# LcsNodes-Main-Controller-Board-B_02_01.net
KiCad netlist of a schematic drawn in EasyEDA
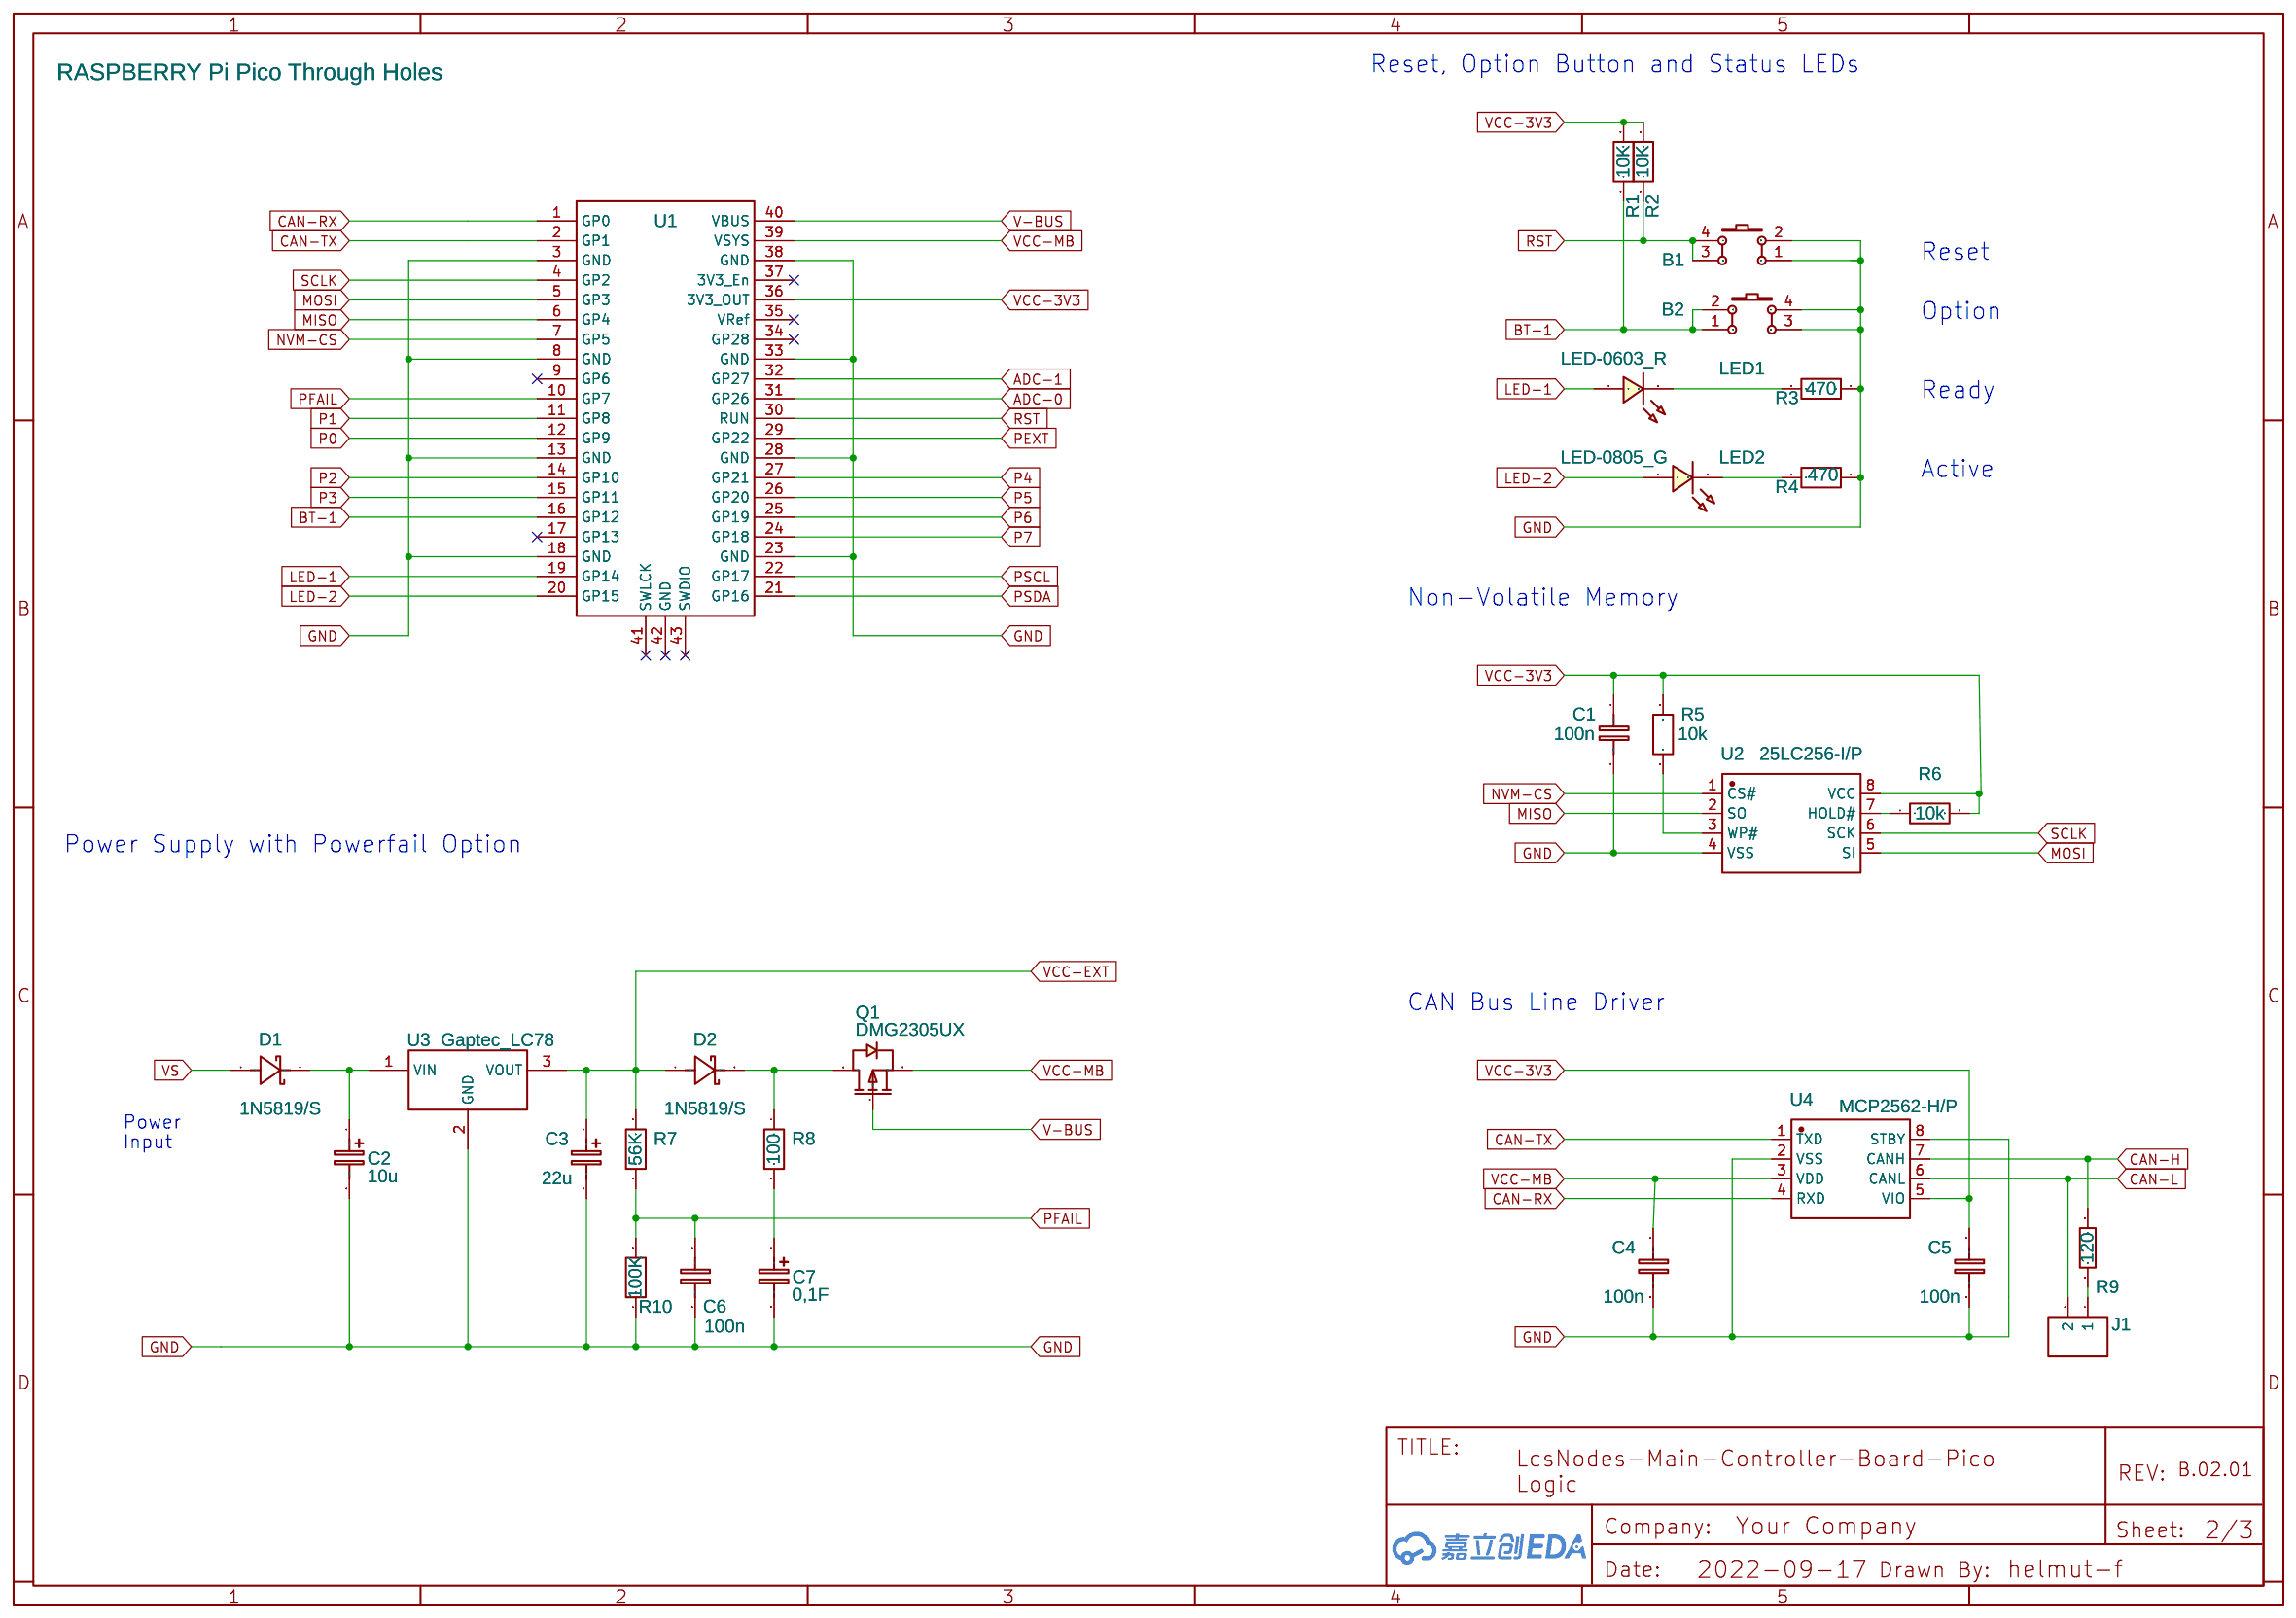
[diagram p0: Controller]
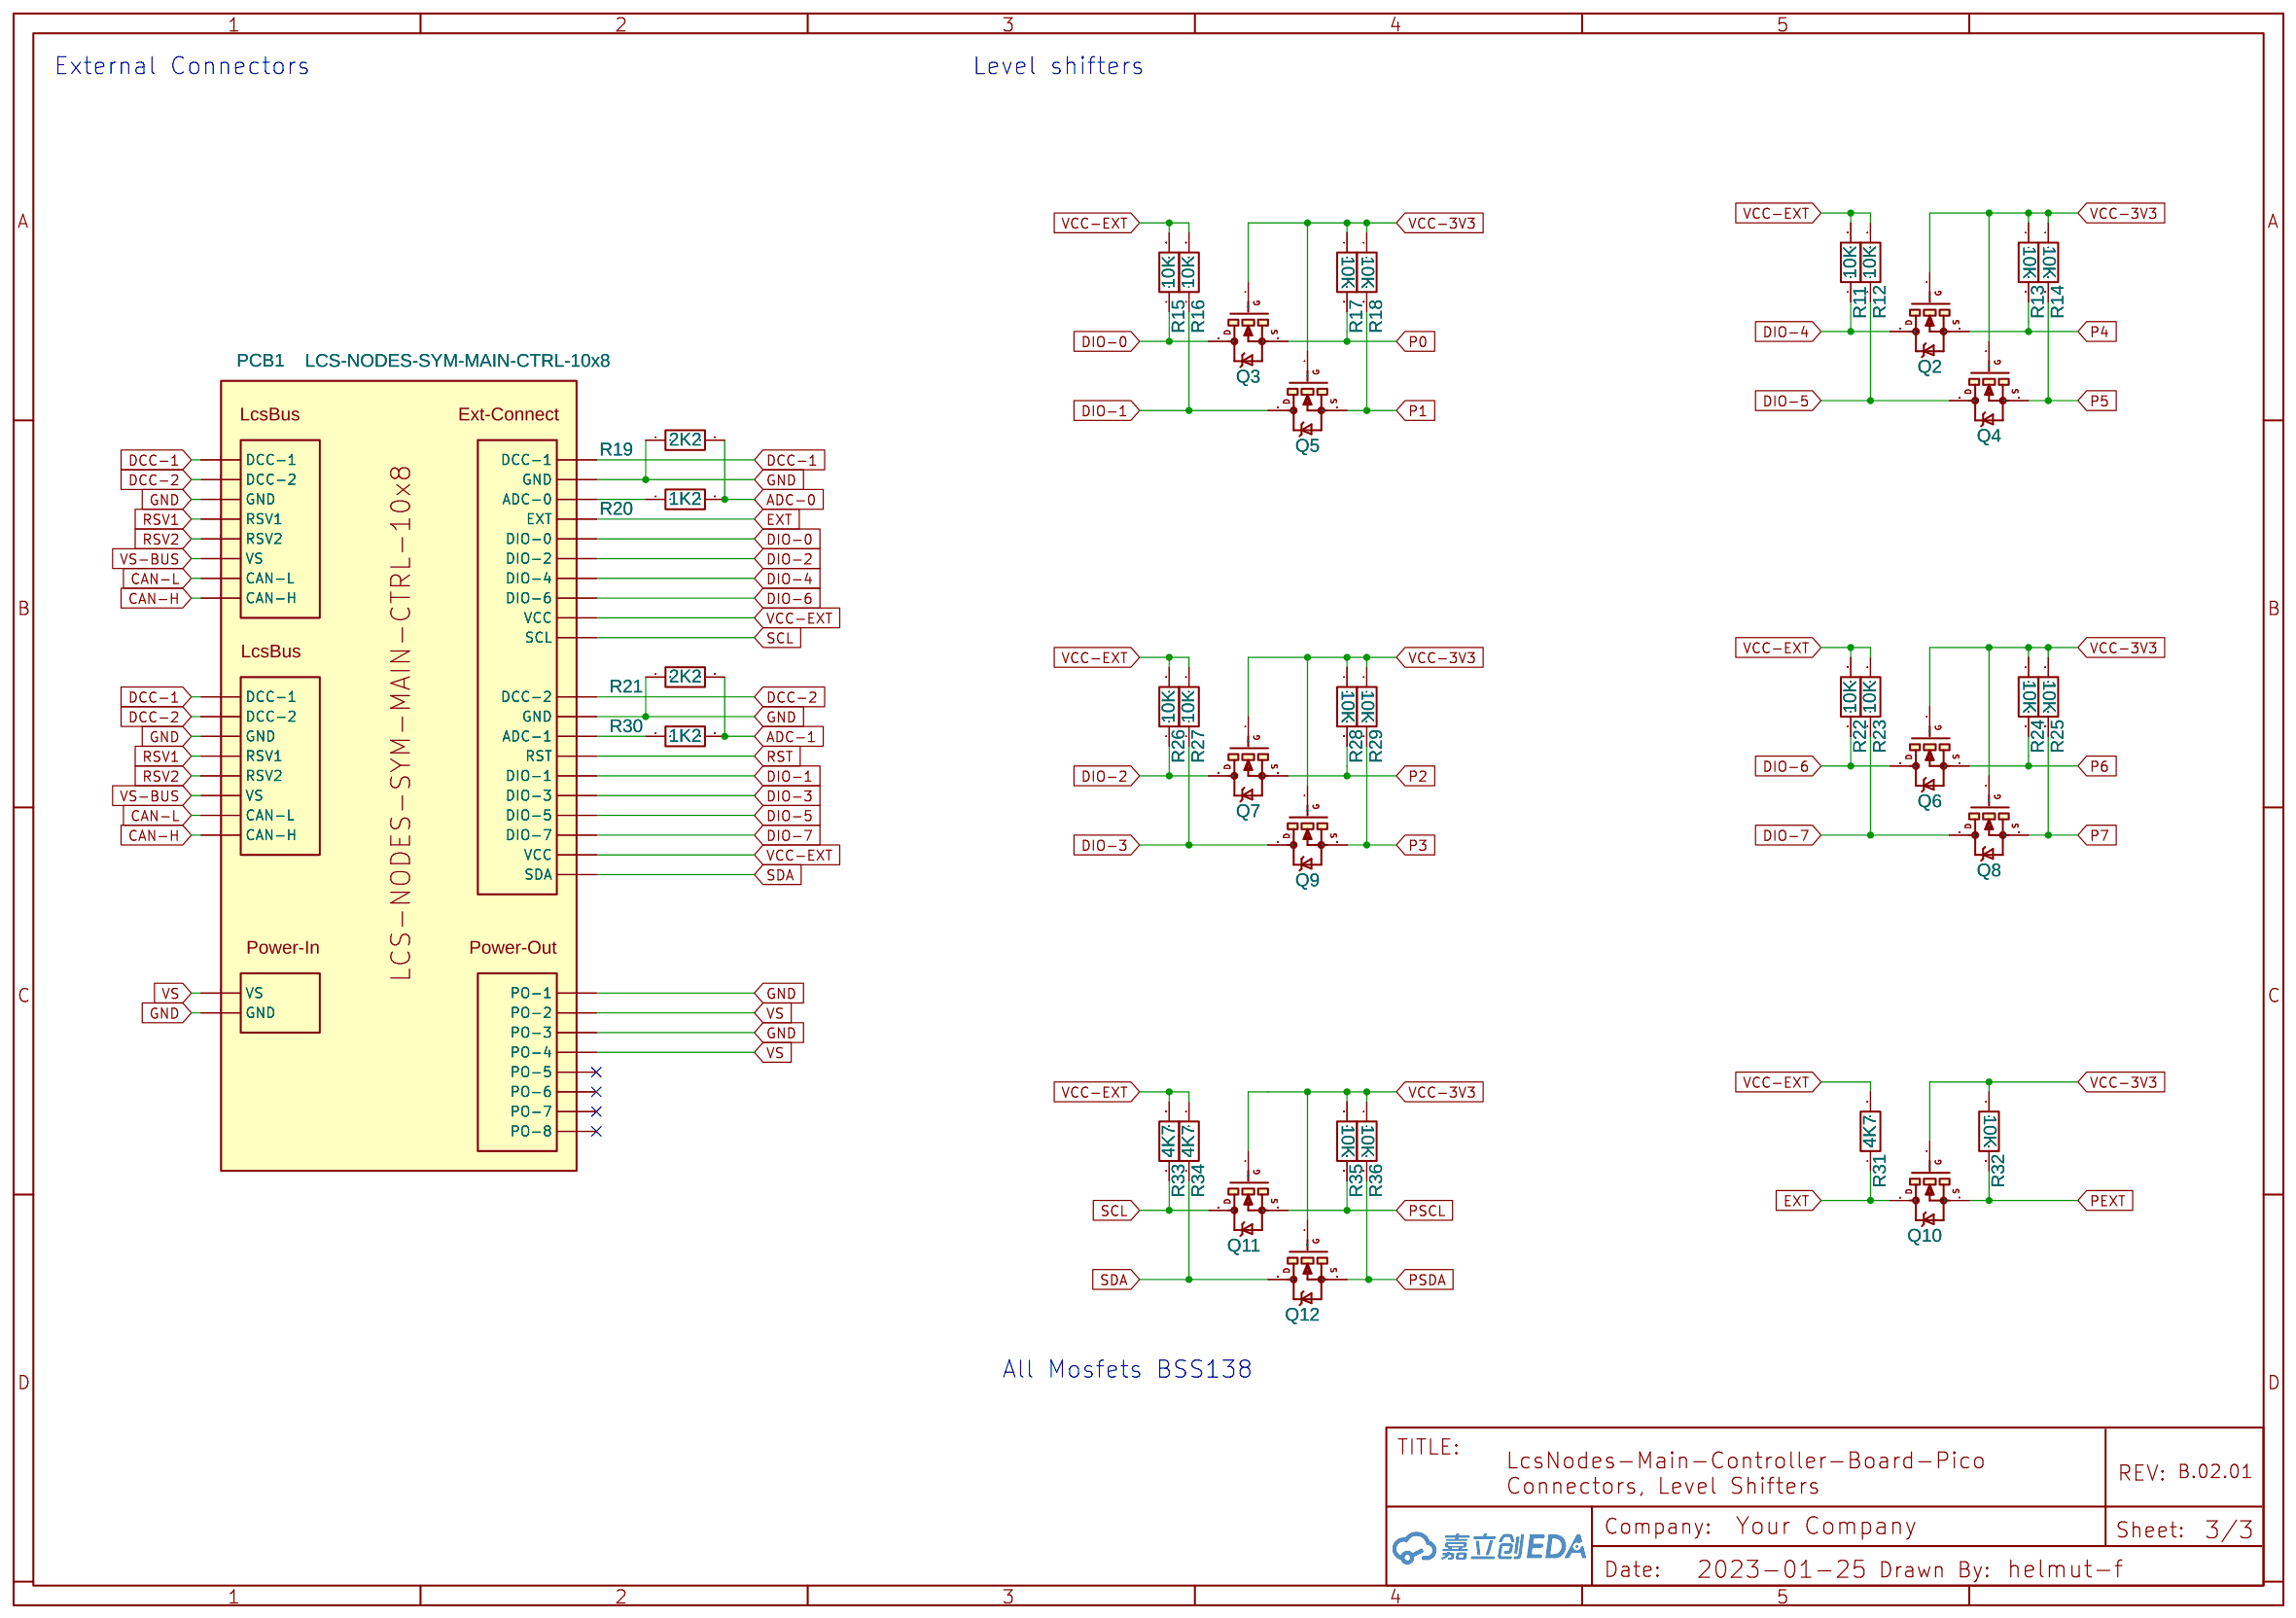
[diagram p1: Connector]
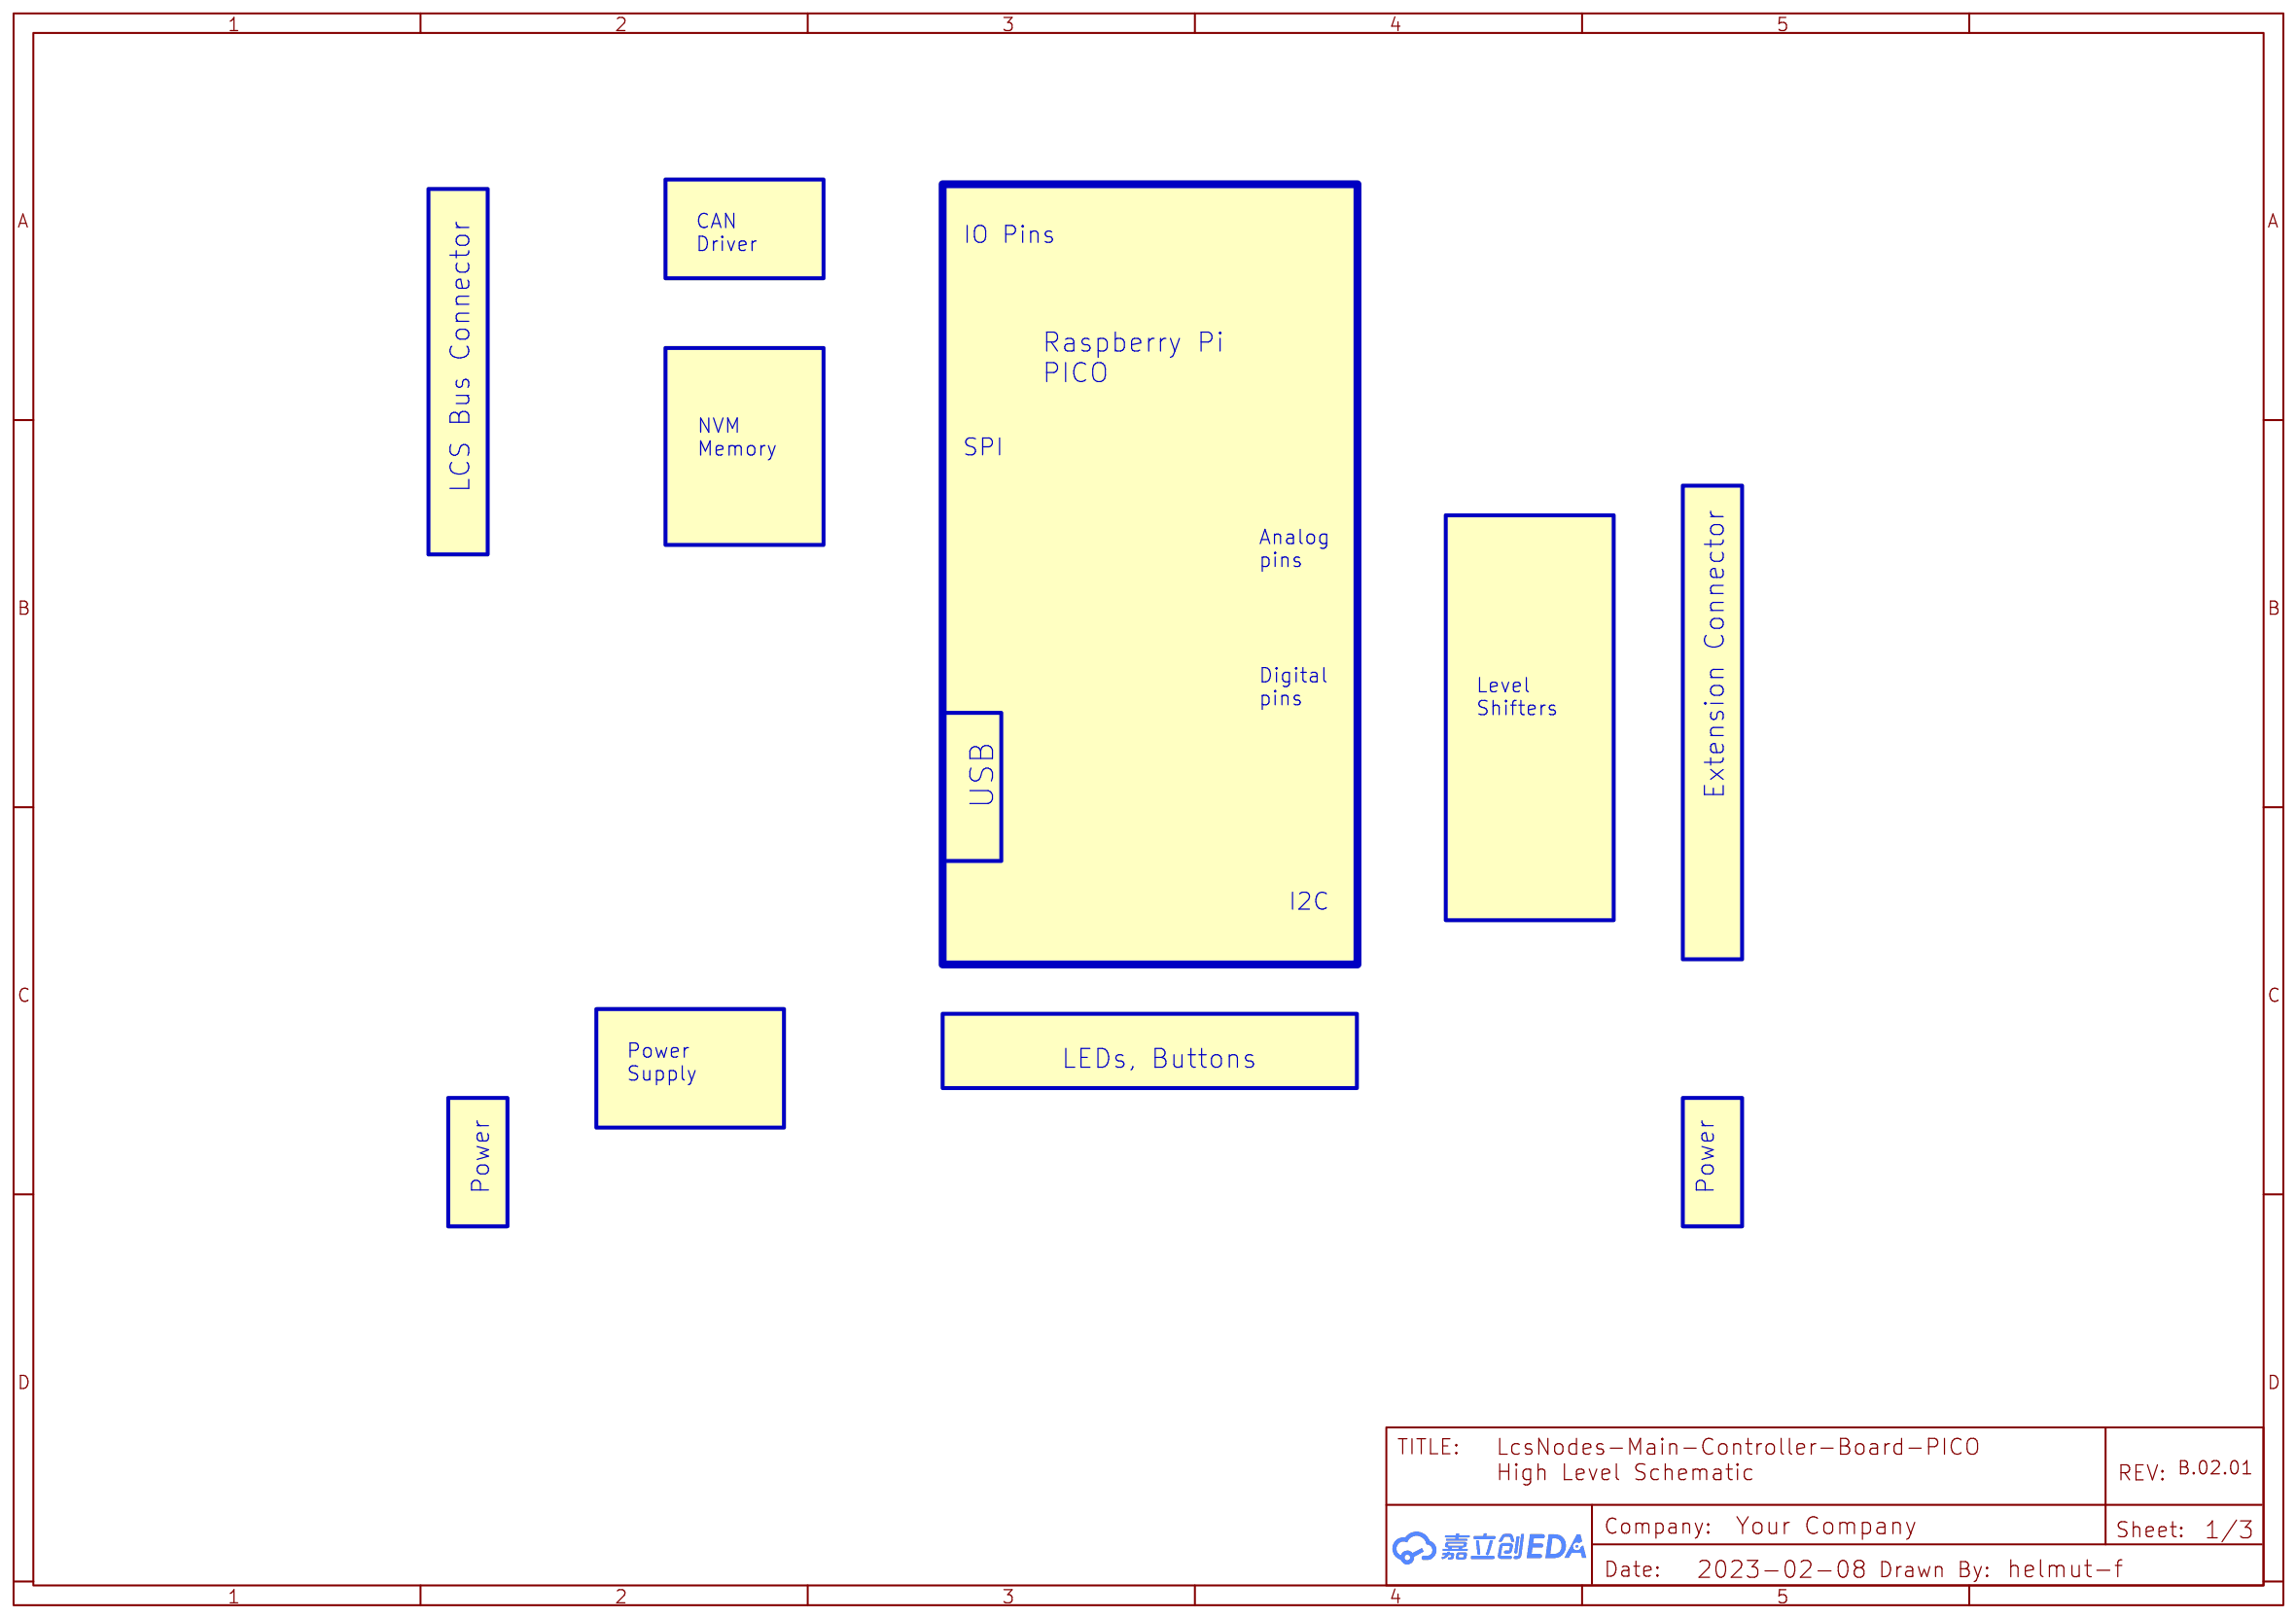
[diagram p2: Block Diagram]

(export (version "E")
  (design (tool "Eeschema 10.0.6"))
  (components
    (comp (ref "B1")
      (value "Reset")
      (fields (field (name "Manufacturer Part") "K2-1102DP-E4SW-04") (field (name "Manufacturer") "韩国韩荣"))
      (libsource (lib "") (part "K4-6×6_TH_1"))
    )
    (comp (ref "B2")
      (value "Opt")
      (fields (field (name "Manufacturer Part") "K2-1102DP-E4SW-04") (field (name "Manufacturer") "韩国韩荣"))
      (libsource (lib "") (part "K4-6×6_TH"))
    )
    (comp (ref "C1") (value "100n") (libsource (lib "") (part "C_0603_EU_1")))
    (comp (ref "C2") (value "10u") (libsource (lib "") (part "CE_SMD_D5.0×H5.5_EU_1")))
    (comp (ref "C3") (value "22u") (libsource (lib "") (part "CE_SMD_D5.0×H5.5_EU")))
    (comp (ref "C4") (value "100n") (libsource (lib "") (part "C_0603_EU")))
    (comp (ref "C5") (value "100n") (libsource (lib "") (part "C_0603_EU")))
    (comp (ref "C6") (value "100n") (libsource (lib "") (part "C_RAD-0.2_EU")))
    (comp (ref "C7") (value "0,1F") (libsource (lib "") (part "C_Tan_SMD_A_EU")))
    (comp (ref "D1") (value "1N5819/S") (libsource (lib "") (part "1N5819/S")))
    (comp (ref "D2") (value "1N5819/S") (libsource (lib "") (part "1N5819/S")))
    (comp (ref "J1") (value "HDR-M-2.54_1x2") (libsource (lib "") (part "HDR-M-2.54_1x2")))
    (comp (ref "LED1")
      (value "LED-0603_R")
      (fields
        (field (name "Manufacturer Part") "19-217/R6C-AL1M2VY/3T")
        (field (name "Manufacturer") "EVERLIGHT(台湾亿光)")
      )
      (libsource (lib "") (part "LED-0603_R"))
    )
    (comp (ref "LED2")
      (value "LED-0805_G")
      (fields (field (name "Manufacturer Part") "NCD0805G1") (field (name "Manufacturer") "国星光电"))
      (libsource (lib "") (part "LED-0805_G"))
    )
    (comp (ref "Q1")
      (value "DMG2305UX")
      (fields (field (name "Manufacturer") "TECH PUBLIC(台舟)"))
      (libsource (lib "") (part "DMG2305UX"))
    )
    (comp (ref "R1") (value "10K") (libsource (lib "") (part "R_0805_EU")))
    (comp (ref "R2") (value "10K") (libsource (lib "") (part "R_0805_EU")))
    (comp (ref "R3") (value "470") (libsource (lib "") (part "R_0805_EU_1")))
    (comp (ref "R4") (value "470") (libsource (lib "") (part "R_0805_EU_1")))
    (comp (ref "R5") (value "10k") (libsource (lib "") (part "R_AXIAL-0.3_EU_2")))
    (comp (ref "R6") (value "10k") (libsource (lib "") (part "R_AXIAL-0.3_EU")))
    (comp (ref "R7") (value "56K") (libsource (lib "") (part "R_AXIAL-0.3_EU_1")))
    (comp (ref "R8") (value "100") (libsource (lib "") (part "R_AXIAL-0.3_EU_2")))
    (comp (ref "R9") (value "120") (libsource (lib "") (part "RESISTOR-AXIAL-0.1")))
    (comp (ref "R10") (value "100K") (libsource (lib "") (part "R_AXIAL-0.3_EU_1")))
    (comp (ref "U1")
      (value "RASPBERRY Pi Pico Through Holes")
      (libsource (lib "") (part "RASPBERRY Pi Pico Through Holes"))
    )
    (comp (ref "U2")
      (value "25LC256-I/P")
      (fields (field (name "Manufacturer") "Microchip Tech"))
      (libsource (lib "") (part "25LC256-I/P"))
    )
    (comp (ref "U3") (value "Gaptec_LC78") (libsource (lib "") (part "Gaptec_LC78")))
    (comp (ref "U4")
      (value "MCP2562-H/P")
      (fields (field (name "Manufacturer") "MICROCHIP(美国微芯)"))
      (libsource (lib "") (part "MCP2562-H/P"))
    )
    (comp (ref "PCB1")
      (value "LCS-NODES-SYM-MAIN-CTRL-10x8")
      (libsource (lib "") (part "LCS-NODES-SYM-MAIN-CTRL-10x8"))
    )
    (comp (ref "Q2") (value "MOSFET-NCHANNELBSS138") (libsource (lib "") (part "MOSFET-NCHANNELBSS138")))
    (comp (ref "Q3") (value "MOSFET-NCHANNELBSS138") (libsource (lib "") (part "MOSFET-NCHANNELBSS138")))
    (comp (ref "Q4") (value "MOSFET-NCHANNELBSS138") (libsource (lib "") (part "MOSFET-NCHANNELBSS138")))
    (comp (ref "Q5") (value "MOSFET-NCHANNELBSS138") (libsource (lib "") (part "MOSFET-NCHANNELBSS138")))
    (comp (ref "Q6") (value "MOSFET-NCHANNELBSS138") (libsource (lib "") (part "MOSFET-NCHANNELBSS138")))
    (comp (ref "Q7") (value "MOSFET-NCHANNELBSS138") (libsource (lib "") (part "MOSFET-NCHANNELBSS138")))
    (comp (ref "Q8") (value "MOSFET-NCHANNELBSS138") (libsource (lib "") (part "MOSFET-NCHANNELBSS138")))
    (comp (ref "Q9") (value "MOSFET-NCHANNELBSS138") (libsource (lib "") (part "MOSFET-NCHANNELBSS138")))
    (comp (ref "Q10") (value "MOSFET-NCHANNELBSS138") (libsource (lib "") (part "MOSFET-NCHANNELBSS138")))
    (comp (ref "Q11") (value "MOSFET-NCHANNELBSS138") (libsource (lib "") (part "MOSFET-NCHANNELBSS138")))
    (comp (ref "Q12") (value "MOSFET-NCHANNELBSS138") (libsource (lib "") (part "MOSFET-NCHANNELBSS138")))
    (comp (ref "R11") (value "10K") (libsource (lib "") (part "R_0805_EU")))
    (comp (ref "R12") (value "10K") (libsource (lib "") (part "R_0805_EU")))
    (comp (ref "R13") (value "10K") (libsource (lib "") (part "R_0805_EU_1")))
    (comp (ref "R14") (value "10K") (libsource (lib "") (part "R_0805_EU_1")))
    (comp (ref "R15") (value "10K") (libsource (lib "") (part "R_0805_EU")))
    (comp (ref "R16") (value "10K") (libsource (lib "") (part "R_0805_EU")))
    (comp (ref "R17") (value "10K") (libsource (lib "") (part "R_0805_EU_1")))
    (comp (ref "R18") (value "10K") (libsource (lib "") (part "R_0805_EU_1")))
    (comp (ref "R19") (value "2K2") (libsource (lib "") (part "R_AXIAL-0.3_EU")))
    (comp (ref "R20") (value "1K2") (libsource (lib "") (part "R_AXIAL-0.3_EU")))
    (comp (ref "R21") (value "2K2") (libsource (lib "") (part "R_AXIAL-0.3_EU")))
    (comp (ref "R22") (value "10K") (libsource (lib "") (part "R_0805_EU")))
    (comp (ref "R23") (value "10K") (libsource (lib "") (part "R_0805_EU")))
    (comp (ref "R24") (value "10K") (libsource (lib "") (part "R_0805_EU_1")))
    (comp (ref "R25") (value "10K") (libsource (lib "") (part "R_0805_EU_1")))
    (comp (ref "R26") (value "10K") (libsource (lib "") (part "R_0805_EU")))
    (comp (ref "R27") (value "10K") (libsource (lib "") (part "R_0805_EU")))
    (comp (ref "R28") (value "10K") (libsource (lib "") (part "R_0805_EU_1")))
    (comp (ref "R29") (value "10K") (libsource (lib "") (part "R_0805_EU_1")))
    (comp (ref "R30") (value "1K2") (libsource (lib "") (part "R_AXIAL-0.3_EU")))
    (comp (ref "R31") (value "4K7") (libsource (lib "") (part "R_0805_EU")))
    (comp (ref "R32") (value "10K") (libsource (lib "") (part "R_0805_EU_1")))
    (comp (ref "R33") (value "4K7") (libsource (lib "") (part "R_0805_EU")))
    (comp (ref "R34") (value "4K7") (libsource (lib "") (part "R_0805_EU")))
    (comp (ref "R35") (value "10K") (libsource (lib "") (part "R_0805_EU_1")))
    (comp (ref "R36") (value "10K") (libsource (lib "") (part "R_0805_EU_1")))
  )
  (nets
    (net (code "1") (name "ADC-0") (class "Default")
      (node (ref "R19") (pin "2") (pinfunction "2_2") (pintype "unspecified"))
      (node (ref "R20") (pin "2") (pinfunction "2_2") (pintype "unspecified"))
      (node (ref "U1") (pin "31") (pinfunction "GP26_31") (pintype "unspecified"))
    )
    (net (code "2") (name "ADC-1") (class "Default")
      (node (ref "R21") (pin "2") (pinfunction "2_2") (pintype "unspecified"))
      (node (ref "R30") (pin "2") (pinfunction "2_2") (pintype "unspecified"))
      (node (ref "U1") (pin "32") (pinfunction "GP27_32") (pintype "unspecified"))
    )
    (net (code "3") (name "BT-1") (class "Default")
      (node (ref "B2") (pin "1") (pinfunction "1_1") (pintype "unspecified"))
      (node (ref "B2") (pin "2") (pinfunction "2_2") (pintype "unspecified"))
      (node (ref "R1") (pin "1") (pinfunction "1_1") (pintype "unspecified"))
      (node (ref "U1") (pin "16") (pinfunction "GP12_16") (pintype "unspecified"))
    )
    (net (code "4") (name "CAN-H") (class "Default")
      (node (ref "PCB1") (pin "18") (pinfunction "CAN-H_18") (pintype "unspecified"))
      (node (ref "PCB1") (pin "8") (pinfunction "CAN-H_8") (pintype "unspecified"))
      (node (ref "R9") (pin "1") (pinfunction "1_1") (pintype "input"))
      (node (ref "U4") (pin "7") (pinfunction "CANH_7") (pintype "unspecified"))
    )
    (net (code "5") (name "CAN-L") (class "Default")
      (node (ref "J1") (pin "2") (pinfunction "2_2") (pintype "unspecified"))
      (node (ref "PCB1") (pin "17") (pinfunction "CAN-L_17") (pintype "unspecified"))
      (node (ref "PCB1") (pin "7") (pinfunction "CAN-L_7") (pintype "unspecified"))
      (node (ref "U4") (pin "6") (pinfunction "CANL_6") (pintype "unspecified"))
    )
    (net (code "6") (name "CAN-RX") (class "Default")
      (node (ref "U1") (pin "1") (pinfunction "GP0_1") (pintype "unspecified"))
      (node (ref "U4") (pin "4") (pinfunction "RXD_4") (pintype "unspecified"))
    )
    (net (code "7") (name "CAN-TX") (class "Default")
      (node (ref "U1") (pin "2") (pinfunction "GP1_2") (pintype "unspecified"))
      (node (ref "U4") (pin "1") (pinfunction "TXD_1") (pintype "unspecified"))
    )
    (net (code "8") (name "DCC-1") (class "Default")
      (node (ref "PCB1") (pin "1") (pinfunction "DCC-1_1") (pintype "unspecified"))
      (node (ref "PCB1") (pin "11") (pinfunction "DCC-1_11") (pintype "unspecified"))
      (node (ref "PCB1") (pin "30") (pinfunction "DCC-1_30") (pintype "unspecified"))
    )
    (net (code "9") (name "DCC-2") (class "Default")
      (node (ref "PCB1") (pin "12") (pinfunction "DCC-2_12") (pintype "unspecified"))
      (node (ref "PCB1") (pin "2") (pinfunction "DCC-2_2") (pintype "unspecified"))
      (node (ref "PCB1") (pin "40") (pinfunction "DCC-2_40") (pintype "unspecified"))
    )
    (net (code "10") (name "DIO-0") (class "Default")
      (node (ref "PCB1") (pin "34") (pinfunction "DIO-0_34") (pintype "unspecified"))
      (node (ref "Q3") (pin "3") (pinfunction "D_3") (pintype "unspecified"))
      (node (ref "R15") (pin "1") (pinfunction "1_1") (pintype "unspecified"))
    )
    (net (code "11") (name "DIO-1") (class "Default")
      (node (ref "PCB1") (pin "44") (pinfunction "DIO-1_44") (pintype "unspecified"))
      (node (ref "Q5") (pin "3") (pinfunction "D_3") (pintype "unspecified"))
      (node (ref "R16") (pin "1") (pinfunction "1_1") (pintype "unspecified"))
    )
    (net (code "12") (name "DIO-2") (class "Default")
      (node (ref "PCB1") (pin "35") (pinfunction "DIO-2_35") (pintype "unspecified"))
      (node (ref "Q7") (pin "3") (pinfunction "D_3") (pintype "unspecified"))
      (node (ref "R26") (pin "1") (pinfunction "1_1") (pintype "unspecified"))
    )
    (net (code "13") (name "DIO-3") (class "Default")
      (node (ref "PCB1") (pin "45") (pinfunction "DIO-3_45") (pintype "unspecified"))
      (node (ref "Q9") (pin "3") (pinfunction "D_3") (pintype "unspecified"))
      (node (ref "R27") (pin "1") (pinfunction "1_1") (pintype "unspecified"))
    )
    (net (code "14") (name "DIO-4") (class "Default")
      (node (ref "PCB1") (pin "36") (pinfunction "DIO-4_36") (pintype "unspecified"))
      (node (ref "Q2") (pin "3") (pinfunction "D_3") (pintype "unspecified"))
      (node (ref "R11") (pin "1") (pinfunction "1_1") (pintype "unspecified"))
    )
    (net (code "15") (name "DIO-5") (class "Default")
      (node (ref "PCB1") (pin "46") (pinfunction "DIO-5_46") (pintype "unspecified"))
      (node (ref "Q4") (pin "3") (pinfunction "D_3") (pintype "unspecified"))
      (node (ref "R12") (pin "1") (pinfunction "1_1") (pintype "unspecified"))
    )
    (net (code "16") (name "DIO-6") (class "Default")
      (node (ref "PCB1") (pin "37") (pinfunction "DIO-6_37") (pintype "unspecified"))
      (node (ref "Q6") (pin "3") (pinfunction "D_3") (pintype "unspecified"))
      (node (ref "R22") (pin "1") (pinfunction "1_1") (pintype "unspecified"))
    )
    (net (code "17") (name "DIO-7") (class "Default")
      (node (ref "PCB1") (pin "47") (pinfunction "DIO-7_47") (pintype "unspecified"))
      (node (ref "Q8") (pin "3") (pinfunction "D_3") (pintype "unspecified"))
      (node (ref "R23") (pin "1") (pinfunction "1_1") (pintype "unspecified"))
    )
    (net (code "18") (name "EXT") (class "Default")
      (node (ref "PCB1") (pin "33") (pinfunction "EXT_33") (pintype "unspecified"))
      (node (ref "Q10") (pin "3") (pinfunction "D_3") (pintype "unspecified"))
      (node (ref "R31") (pin "1") (pinfunction "1_1") (pintype "unspecified"))
    )
    (net (code "19") (name "GND") (class "Default")
      (node (ref "B1") (pin "1") (pinfunction "1_1") (pintype "unspecified"))
      (node (ref "B1") (pin "2") (pinfunction "2_2") (pintype "unspecified"))
      (node (ref "B2") (pin "3") (pinfunction "3_3") (pintype "unspecified"))
      (node (ref "B2") (pin "4") (pinfunction "4_4") (pintype "unspecified"))
      (node (ref "C1") (pin "2") (pinfunction "2_2") (pintype "unspecified"))
      (node (ref "C2") (pin "2") (pinfunction "2_2") (pintype "unspecified"))
      (node (ref "C3") (pin "2") (pinfunction "2_2") (pintype "unspecified"))
      (node (ref "C4") (pin "2") (pinfunction "2_2") (pintype "unspecified"))
      (node (ref "C5") (pin "2") (pinfunction "2_2") (pintype "unspecified"))
      (node (ref "C6") (pin "2") (pinfunction "2_2") (pintype "unspecified"))
      (node (ref "C7") (pin "2") (pinfunction "2_2") (pintype "unspecified"))
      (node (ref "PCB1") (pin "13") (pinfunction "GND_13") (pintype "unspecified"))
      (node (ref "PCB1") (pin "21") (pinfunction "GND_21") (pintype "unspecified"))
      (node (ref "PCB1") (pin "3") (pinfunction "GND_3") (pintype "unspecified"))
      (node (ref "PCB1") (pin "31") (pinfunction "GND_31") (pintype "unspecified"))
      (node (ref "PCB1") (pin "41") (pinfunction "GND_41") (pintype "unspecified"))
      (node (ref "PCB1") (pin "50") (pinfunction "PO-1_50") (pintype "unspecified"))
      (node (ref "PCB1") (pin "51") (pinfunction "PO-3_51") (pintype "unspecified"))
      (node (ref "R10") (pin "1") (pinfunction "1_1") (pintype "unspecified"))
      (node (ref "R19") (pin "1") (pinfunction "1_1") (pintype "unspecified"))
      (node (ref "R21") (pin "1") (pinfunction "1_1") (pintype "unspecified"))
      (node (ref "R3") (pin "1") (pinfunction "1_1") (pintype "unspecified"))
      (node (ref "R4") (pin "1") (pinfunction "1_1") (pintype "unspecified"))
      (node (ref "U1") (pin "13") (pinfunction "GND_13") (pintype "unspecified"))
      (node (ref "U1") (pin "18") (pinfunction "GND_18") (pintype "unspecified"))
      (node (ref "U1") (pin "23") (pinfunction "GND_23") (pintype "unspecified"))
      (node (ref "U1") (pin "28") (pinfunction "GND_28") (pintype "unspecified"))
      (node (ref "U1") (pin "3") (pinfunction "GND_3") (pintype "unspecified"))
      (node (ref "U1") (pin "33") (pinfunction "GND_33") (pintype "unspecified"))
      (node (ref "U1") (pin "38") (pinfunction "GND_38") (pintype "unspecified"))
      (node (ref "U1") (pin "8") (pinfunction "GND_8") (pintype "unspecified"))
      (node (ref "U2") (pin "4") (pinfunction "VSS_4") (pintype "unspecified"))
      (node (ref "U3") (pin "2") (pinfunction "GND_2") (pintype "unspecified"))
      (node (ref "U4") (pin "2") (pinfunction "VSS_2") (pintype "unspecified"))
      (node (ref "U4") (pin "8") (pinfunction "STBY_8") (pintype "unspecified"))
    )
    (net (code "20") (name "LED-1") (class "Default")
      (node (ref "LED1") (pin "1") (pinfunction "1_1") (pintype "unspecified"))
      (node (ref "U1") (pin "19") (pinfunction "GP14_19") (pintype "unspecified"))
    )
    (net (code "21") (name "LED-2") (class "Default")
      (node (ref "LED2") (pin "1") (pinfunction "1_1") (pintype "unspecified"))
      (node (ref "U1") (pin "20") (pinfunction "GP15_20") (pintype "unspecified"))
    )
    (net (code "22") (name "MISO") (class "Default")
      (node (ref "U1") (pin "6") (pinfunction "GP4_6") (pintype "unspecified"))
      (node (ref "U2") (pin "2") (pinfunction "SO_2") (pintype "unspecified"))
    )
    (net (code "23") (name "MOSI") (class "Default")
      (node (ref "U1") (pin "5") (pinfunction "GP3_5") (pintype "unspecified"))
      (node (ref "U2") (pin "5") (pinfunction "SI_5") (pintype "unspecified"))
    )
    (net (code "24") (name "NVM-CS") (class "Default")
      (node (ref "U1") (pin "7") (pinfunction "GP5_7") (pintype "unspecified"))
      (node (ref "U2") (pin "1") (pinfunction "CS#_1") (pintype "unspecified"))
    )
    (net (code "25") (name "Net-(C7-Pad1)") (class "Default")
      (node (ref "C7") (pin "1") (pinfunction "1_1") (pintype "unspecified"))
      (node (ref "R8") (pin "2") (pinfunction "2_2") (pintype "unspecified"))
    )
    (net (code "26") (name "Net-(D1-K)") (class "Default")
      (node (ref "C2") (pin "1") (pinfunction "1_1") (pintype "unspecified"))
      (node (ref "D1") (pin "2") (pinfunction "K_2") (pintype "unspecified"))
      (node (ref "U3") (pin "1") (pinfunction "VIN_1") (pintype "unspecified"))
    )
    (net (code "27") (name "Net-(D2-K)") (class "Default")
      (node (ref "D2") (pin "2") (pinfunction "K_2") (pintype "unspecified"))
      (node (ref "Q1") (pin "3") (pinfunction "D_3") (pintype "unspecified"))
      (node (ref "R8") (pin "1") (pinfunction "1_1") (pintype "unspecified"))
    )
    (net (code "28") (name "Net-(J1-Pad1)") (class "Default")
      (node (ref "J1") (pin "1") (pinfunction "1_1") (pintype "unspecified"))
      (node (ref "R9") (pin "2") (pinfunction "2_2") (pintype "input"))
    )
    (net (code "29") (name "Net-(LED1-Pad2)") (class "Default")
      (node (ref "LED1") (pin "2") (pinfunction "2_2") (pintype "unspecified"))
      (node (ref "R3") (pin "2") (pinfunction "2_2") (pintype "unspecified"))
    )
    (net (code "30") (name "Net-(LED2-Pad2)") (class "Default")
      (node (ref "LED2") (pin "2") (pinfunction "2_2") (pintype "unspecified"))
      (node (ref "R4") (pin "2") (pinfunction "2_2") (pintype "unspecified"))
    )
    (net (code "31") (name "Net-(PCB1-ADC-0)") (class "Default")
      (node (ref "PCB1") (pin "32") (pinfunction "ADC-0_32") (pintype "unspecified"))
      (node (ref "R20") (pin "1") (pinfunction "1_1") (pintype "unspecified"))
    )
    (net (code "32") (name "Net-(PCB1-ADC-1)") (class "Default")
      (node (ref "PCB1") (pin "42") (pinfunction "ADC-1_42") (pintype "unspecified"))
      (node (ref "R30") (pin "1") (pinfunction "1_1") (pintype "unspecified"))
    )
    (net (code "33") (name "Net-(U2-HOLD#)") (class "Default")
      (node (ref "R6") (pin "1") (pinfunction "1_1") (pintype "unspecified"))
      (node (ref "U2") (pin "7") (pinfunction "HOLD#_7") (pintype "unspecified"))
    )
    (net (code "34") (name "Net-(U2-WP#)") (class "Default")
      (node (ref "R5") (pin "2") (pinfunction "2_2") (pintype "unspecified"))
      (node (ref "U2") (pin "3") (pinfunction "WP#_3") (pintype "unspecified"))
    )
    (net (code "35") (name "P0") (class "Default")
      (node (ref "Q3") (pin "2") (pinfunction "S_2") (pintype "unspecified"))
      (node (ref "R17") (pin "2") (pinfunction "2_2") (pintype "unspecified"))
      (node (ref "U1") (pin "12") (pinfunction "GP9_12") (pintype "unspecified"))
    )
    (net (code "36") (name "P1") (class "Default")
      (node (ref "Q5") (pin "2") (pinfunction "S_2") (pintype "unspecified"))
      (node (ref "R18") (pin "2") (pinfunction "2_2") (pintype "unspecified"))
      (node (ref "U1") (pin "11") (pinfunction "GP8_11") (pintype "unspecified"))
    )
    (net (code "37") (name "P2") (class "Default")
      (node (ref "Q7") (pin "2") (pinfunction "S_2") (pintype "unspecified"))
      (node (ref "R28") (pin "2") (pinfunction "2_2") (pintype "unspecified"))
      (node (ref "U1") (pin "14") (pinfunction "GP10_14") (pintype "unspecified"))
    )
    (net (code "38") (name "P3") (class "Default")
      (node (ref "Q9") (pin "2") (pinfunction "S_2") (pintype "unspecified"))
      (node (ref "R29") (pin "2") (pinfunction "2_2") (pintype "unspecified"))
      (node (ref "U1") (pin "15") (pinfunction "GP11_15") (pintype "unspecified"))
    )
    (net (code "39") (name "P4") (class "Default")
      (node (ref "Q2") (pin "2") (pinfunction "S_2") (pintype "unspecified"))
      (node (ref "R13") (pin "2") (pinfunction "2_2") (pintype "unspecified"))
      (node (ref "U1") (pin "27") (pinfunction "GP21_27") (pintype "unspecified"))
    )
    (net (code "40") (name "P5") (class "Default")
      (node (ref "Q4") (pin "2") (pinfunction "S_2") (pintype "unspecified"))
      (node (ref "R14") (pin "2") (pinfunction "2_2") (pintype "unspecified"))
      (node (ref "U1") (pin "26") (pinfunction "GP20_26") (pintype "unspecified"))
    )
    (net (code "41") (name "P6") (class "Default")
      (node (ref "Q6") (pin "2") (pinfunction "S_2") (pintype "unspecified"))
      (node (ref "R24") (pin "2") (pinfunction "2_2") (pintype "unspecified"))
      (node (ref "U1") (pin "25") (pinfunction "GP19_25") (pintype "unspecified"))
    )
    (net (code "42") (name "P7") (class "Default")
      (node (ref "Q8") (pin "2") (pinfunction "S_2") (pintype "unspecified"))
      (node (ref "R25") (pin "2") (pinfunction "2_2") (pintype "unspecified"))
      (node (ref "U1") (pin "24") (pinfunction "GP18_24") (pintype "unspecified"))
    )
    (net (code "43") (name "PEXT") (class "Default")
      (node (ref "Q10") (pin "2") (pinfunction "S_2") (pintype "unspecified"))
      (node (ref "R32") (pin "2") (pinfunction "2_2") (pintype "unspecified"))
      (node (ref "U1") (pin "29") (pinfunction "GP22_29") (pintype "unspecified"))
    )
    (net (code "44") (name "PFAIL") (class "Default")
      (node (ref "C6") (pin "1") (pinfunction "1_1") (pintype "unspecified"))
      (node (ref "R10") (pin "2") (pinfunction "2_2") (pintype "unspecified"))
      (node (ref "R7") (pin "1") (pinfunction "1_1") (pintype "unspecified"))
      (node (ref "U1") (pin "10") (pinfunction "GP7_10") (pintype "unspecified"))
    )
    (net (code "45") (name "PSCL") (class "Default")
      (node (ref "Q11") (pin "2") (pinfunction "S_2") (pintype "unspecified"))
      (node (ref "R35") (pin "2") (pinfunction "2_2") (pintype "unspecified"))
      (node (ref "U1") (pin "22") (pinfunction "GP17_22") (pintype "unspecified"))
    )
    (net (code "46") (name "PSDA") (class "Default")
      (node (ref "Q12") (pin "2") (pinfunction "S_2") (pintype "unspecified"))
      (node (ref "R36") (pin "2") (pinfunction "2_2") (pintype "unspecified"))
      (node (ref "U1") (pin "21") (pinfunction "GP16_21") (pintype "unspecified"))
    )
    (net (code "47") (name "RST") (class "Default")
      (node (ref "B1") (pin "3") (pinfunction "3_3") (pintype "unspecified"))
      (node (ref "B1") (pin "4") (pinfunction "4_4") (pintype "unspecified"))
      (node (ref "PCB1") (pin "43") (pinfunction "RST_43") (pintype "unspecified"))
      (node (ref "R2") (pin "1") (pinfunction "1_1") (pintype "unspecified"))
      (node (ref "U1") (pin "30") (pinfunction "RUN_30") (pintype "unspecified"))
    )
    (net (code "48") (name "RSV1") (class "Default")
      (node (ref "PCB1") (pin "14") (pinfunction "RSV1_14") (pintype "unspecified"))
      (node (ref "PCB1") (pin "4") (pinfunction "RSV1_4") (pintype "unspecified"))
    )
    (net (code "49") (name "RSV2") (class "Default")
      (node (ref "PCB1") (pin "15") (pinfunction "RSV2_15") (pintype "unspecified"))
      (node (ref "PCB1") (pin "5") (pinfunction "RSV2_5") (pintype "unspecified"))
    )
    (net (code "50") (name "SCL") (class "Default")
      (node (ref "PCB1") (pin "39") (pinfunction "SCL_39") (pintype "unspecified"))
      (node (ref "Q11") (pin "3") (pinfunction "D_3") (pintype "unspecified"))
      (node (ref "R33") (pin "1") (pinfunction "1_1") (pintype "unspecified"))
    )
    (net (code "51") (name "SCLK") (class "Default")
      (node (ref "U1") (pin "4") (pinfunction "GP2_4") (pintype "unspecified"))
      (node (ref "U2") (pin "6") (pinfunction "SCK_6") (pintype "unspecified"))
    )
    (net (code "52") (name "SDA") (class "Default")
      (node (ref "PCB1") (pin "49") (pinfunction "SDA_49") (pintype "unspecified"))
      (node (ref "Q12") (pin "3") (pinfunction "D_3") (pintype "unspecified"))
      (node (ref "R34") (pin "1") (pinfunction "1_1") (pintype "unspecified"))
    )
    (net (code "53") (name "V-BUS") (class "Default")
      (node (ref "Q1") (pin "1") (pinfunction "G_1") (pintype "unspecified"))
      (node (ref "U1") (pin "40") (pinfunction "VBUS_40") (pintype "unspecified"))
    )
    (net (code "54") (name "VCC-3V3") (class "Default")
      (node (ref "C1") (pin "1") (pinfunction "1_1") (pintype "unspecified"))
      (node (ref "C5") (pin "1") (pinfunction "1_1") (pintype "unspecified"))
      (node (ref "Q10") (pin "1") (pinfunction "G_1") (pintype "unspecified"))
      (node (ref "Q11") (pin "1") (pinfunction "G_1") (pintype "unspecified"))
      (node (ref "Q12") (pin "1") (pinfunction "G_1") (pintype "unspecified"))
      (node (ref "Q2") (pin "1") (pinfunction "G_1") (pintype "unspecified"))
      (node (ref "Q3") (pin "1") (pinfunction "G_1") (pintype "unspecified"))
      (node (ref "Q4") (pin "1") (pinfunction "G_1") (pintype "unspecified"))
      (node (ref "Q5") (pin "1") (pinfunction "G_1") (pintype "unspecified"))
      (node (ref "Q6") (pin "1") (pinfunction "G_1") (pintype "unspecified"))
      (node (ref "Q7") (pin "1") (pinfunction "G_1") (pintype "unspecified"))
      (node (ref "Q8") (pin "1") (pinfunction "G_1") (pintype "unspecified"))
      (node (ref "Q9") (pin "1") (pinfunction "G_1") (pintype "unspecified"))
      (node (ref "R1") (pin "2") (pinfunction "2_2") (pintype "unspecified"))
      (node (ref "R13") (pin "1") (pinfunction "1_1") (pintype "unspecified"))
      (node (ref "R14") (pin "1") (pinfunction "1_1") (pintype "unspecified"))
      (node (ref "R17") (pin "1") (pinfunction "1_1") (pintype "unspecified"))
      (node (ref "R18") (pin "1") (pinfunction "1_1") (pintype "unspecified"))
      (node (ref "R2") (pin "2") (pinfunction "2_2") (pintype "unspecified"))
      (node (ref "R24") (pin "1") (pinfunction "1_1") (pintype "unspecified"))
      (node (ref "R25") (pin "1") (pinfunction "1_1") (pintype "unspecified"))
      (node (ref "R28") (pin "1") (pinfunction "1_1") (pintype "unspecified"))
      (node (ref "R29") (pin "1") (pinfunction "1_1") (pintype "unspecified"))
      (node (ref "R32") (pin "1") (pinfunction "1_1") (pintype "unspecified"))
      (node (ref "R35") (pin "1") (pinfunction "1_1") (pintype "unspecified"))
      (node (ref "R36") (pin "1") (pinfunction "1_1") (pintype "unspecified"))
      (node (ref "R5") (pin "1") (pinfunction "1_1") (pintype "unspecified"))
      (node (ref "R6") (pin "2") (pinfunction "2_2") (pintype "unspecified"))
      (node (ref "U1") (pin "36") (pinfunction "3V3_OUT_36") (pintype "unspecified"))
      (node (ref "U2") (pin "8") (pinfunction "VCC_8") (pintype "unspecified"))
      (node (ref "U4") (pin "5") (pinfunction "VIO_5") (pintype "unspecified"))
    )
    (net (code "55") (name "VCC-EXT") (class "Default")
      (node (ref "C3") (pin "1") (pinfunction "1_1") (pintype "unspecified"))
      (node (ref "D2") (pin "1") (pinfunction "A_1") (pintype "unspecified"))
      (node (ref "PCB1") (pin "38") (pinfunction "VCC_38") (pintype "unspecified"))
      (node (ref "PCB1") (pin "48") (pinfunction "VCC_48") (pintype "unspecified"))
      (node (ref "R11") (pin "2") (pinfunction "2_2") (pintype "unspecified"))
      (node (ref "R12") (pin "2") (pinfunction "2_2") (pintype "unspecified"))
      (node (ref "R15") (pin "2") (pinfunction "2_2") (pintype "unspecified"))
      (node (ref "R16") (pin "2") (pinfunction "2_2") (pintype "unspecified"))
      (node (ref "R22") (pin "2") (pinfunction "2_2") (pintype "unspecified"))
      (node (ref "R23") (pin "2") (pinfunction "2_2") (pintype "unspecified"))
      (node (ref "R26") (pin "2") (pinfunction "2_2") (pintype "unspecified"))
      (node (ref "R27") (pin "2") (pinfunction "2_2") (pintype "unspecified"))
      (node (ref "R31") (pin "2") (pinfunction "2_2") (pintype "unspecified"))
      (node (ref "R33") (pin "2") (pinfunction "2_2") (pintype "unspecified"))
      (node (ref "R34") (pin "2") (pinfunction "2_2") (pintype "unspecified"))
      (node (ref "R7") (pin "2") (pinfunction "2_2") (pintype "unspecified"))
      (node (ref "U3") (pin "3") (pinfunction "VOUT_3") (pintype "unspecified"))
    )
    (net (code "56") (name "VCC-MB") (class "Default")
      (node (ref "C4") (pin "1") (pinfunction "1_1") (pintype "unspecified"))
      (node (ref "Q1") (pin "2") (pinfunction "S_2") (pintype "unspecified"))
      (node (ref "U1") (pin "39") (pinfunction "VSYS_39") (pintype "unspecified"))
      (node (ref "U4") (pin "3") (pinfunction "VDD_3") (pintype "unspecified"))
    )
    (net (code "57") (name "VS") (class "Default")
      (node (ref "D1") (pin "1") (pinfunction "A_1") (pintype "unspecified"))
      (node (ref "PCB1") (pin "20") (pinfunction "VS_20") (pintype "unspecified"))
      (node (ref "PCB1") (pin "54") (pinfunction "PO-2_54") (pintype "unspecified"))
      (node (ref "PCB1") (pin "55") (pinfunction "PO-4_55") (pintype "unspecified"))
    )
    (net (code "58") (name "VS-BUS") (class "Default")
      (node (ref "PCB1") (pin "16") (pinfunction "VS_16") (pintype "unspecified"))
      (node (ref "PCB1") (pin "6") (pinfunction "VS_6") (pintype "unspecified"))
    )
    (net (code "59") (name "unconnected-(PCB1-PO-5-Pad52)") (class "Default")
      (node (ref "PCB1") (pin "52") (pinfunction "PO-5_52") (pintype "unspecified+no_connect"))
    )
    (net (code "60") (name "unconnected-(PCB1-PO-6-Pad56)") (class "Default")
      (node (ref "PCB1") (pin "56") (pinfunction "PO-6_56") (pintype "unspecified+no_connect"))
    )
    (net (code "61") (name "unconnected-(PCB1-PO-7-Pad53)") (class "Default")
      (node (ref "PCB1") (pin "53") (pinfunction "PO-7_53") (pintype "unspecified+no_connect"))
    )
    (net (code "62") (name "unconnected-(PCB1-PO-8-Pad57)") (class "Default")
      (node (ref "PCB1") (pin "57") (pinfunction "PO-8_57") (pintype "unspecified+no_connect"))
    )
    (net (code "63") (name "unconnected-(U1-3V3_En-Pad37)") (class "Default")
      (node (ref "U1") (pin "37") (pinfunction "3V3_En_37") (pintype "unspecified+no_connect"))
    )
    (net (code "64") (name "unconnected-(U1-GND-Pad42)") (class "Default")
      (node (ref "U1") (pin "42") (pinfunction "GND_42") (pintype "unspecified+no_connect"))
    )
    (net (code "65") (name "unconnected-(U1-GP6-Pad9)") (class "Default")
      (node (ref "U1") (pin "9") (pinfunction "GP6_9") (pintype "unspecified+no_connect"))
    )
    (net (code "66") (name "unconnected-(U1-GP13-Pad17)") (class "Default")
      (node (ref "U1") (pin "17") (pinfunction "GP13_17") (pintype "unspecified+no_connect"))
    )
    (net (code "67") (name "unconnected-(U1-GP28-Pad34)") (class "Default")
      (node (ref "U1") (pin "34") (pinfunction "GP28_34") (pintype "unspecified+no_connect"))
    )
    (net (code "68") (name "unconnected-(U1-SWDIO-Pad43)") (class "Default")
      (node (ref "U1") (pin "43") (pinfunction "SWDIO_43") (pintype "unspecified+no_connect"))
    )
    (net (code "69") (name "unconnected-(U1-SWLCK-Pad41)") (class "Default")
      (node (ref "U1") (pin "41") (pinfunction "SWLCK_41") (pintype "unspecified+no_connect"))
    )
    (net (code "70") (name "unconnected-(U1-VRef-Pad35)") (class "Default")
      (node (ref "U1") (pin "35") (pinfunction "VRef_35") (pintype "unspecified+no_connect"))
    )
  )
)
